# PSU-triple-voltage.net
KiCad netlist of a schematic drawn in EAGLE
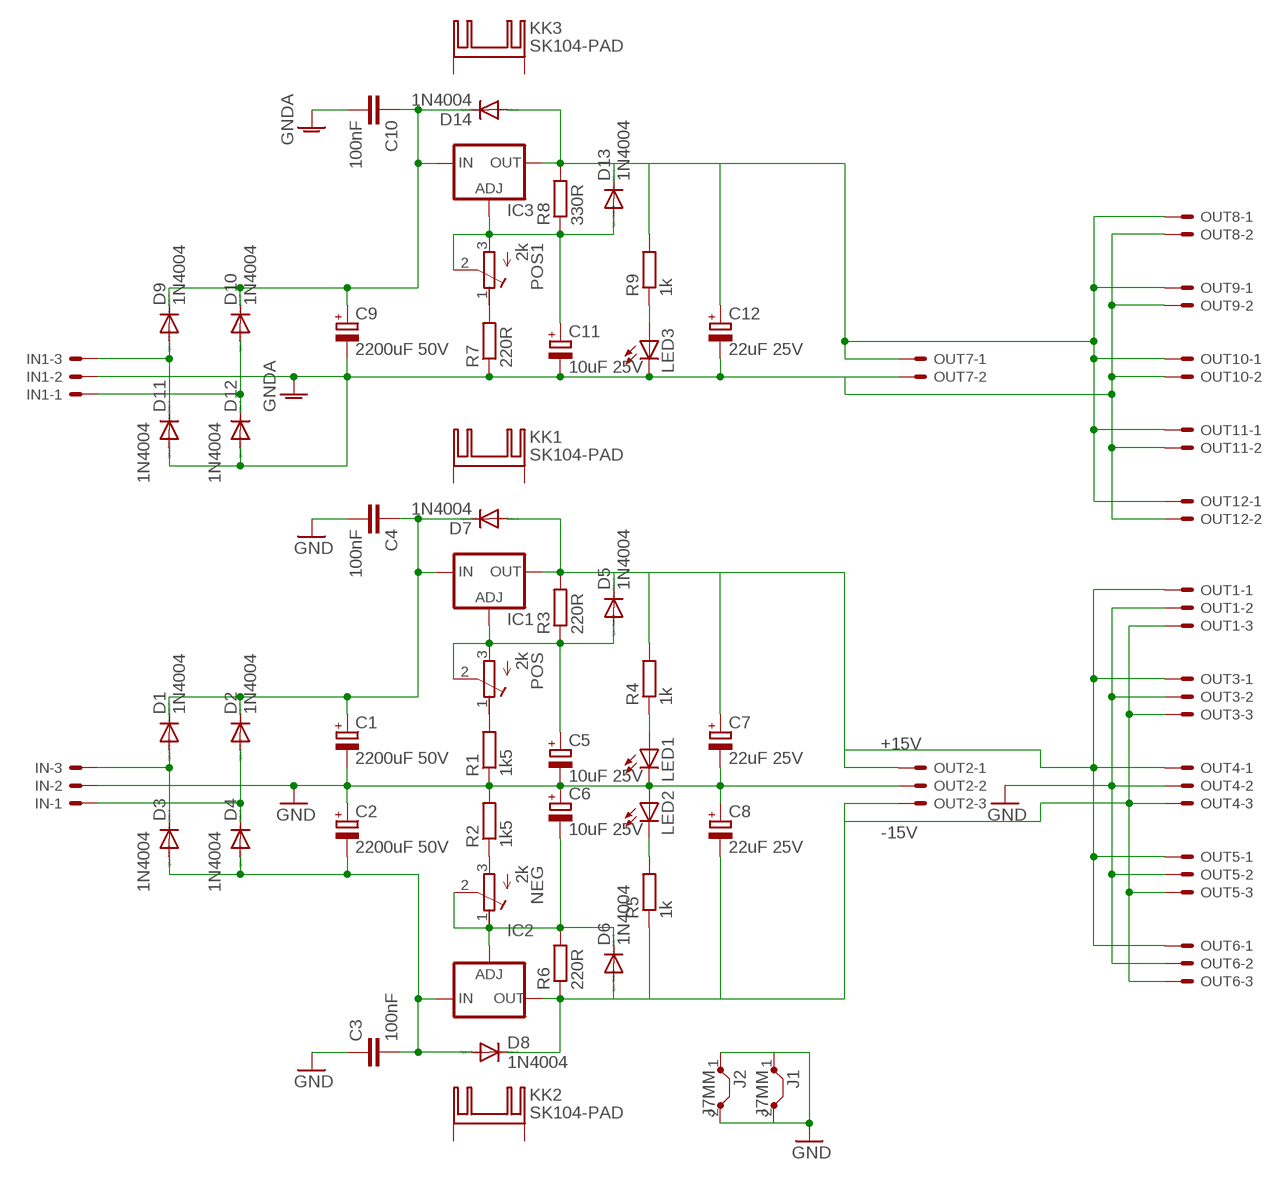
[diagram p0: schematic, sheet 1]

(export (version "E")
  (design (tool "Eeschema 10.0.6"))
  (components
    (comp (ref "C1")
      (value "2200uF 50V")
      (footprint "eagle-import:E7,5-16")
      (libsource (lib "eagle-import") (part "CPOL-EUE7.5-16"))
    )
    (comp (ref "C2")
      (value "2200uF 50V")
      (footprint "eagle-import:E7,5-16")
      (libsource (lib "eagle-import") (part "CPOL-EUE7.5-16"))
    )
    (comp (ref "C3")
      (value "100nF")
      (footprint "eagle-import:C050-025X075")
      (libsource (lib "eagle-import") (part "C-EU050-025X075"))
    )
    (comp (ref "C4")
      (value "100nF")
      (footprint "eagle-import:C050-025X075")
      (libsource (lib "eagle-import") (part "C-EU050-025X075"))
    )
    (comp (ref "C5")
      (value "10uF 25V")
      (footprint "eagle-import:E2,5-5")
      (libsource (lib "eagle-import") (part "CPOL-EUE2.5-5"))
    )
    (comp (ref "C6")
      (value "10uF 25V")
      (footprint "eagle-import:E2,5-5")
      (libsource (lib "eagle-import") (part "CPOL-EUE2.5-5"))
    )
    (comp (ref "C7")
      (value "22uF 25V")
      (footprint "eagle-import:E2,5-5")
      (libsource (lib "eagle-import") (part "CPOL-EUE2.5-5"))
    )
    (comp (ref "C8")
      (value "22uF 25V")
      (footprint "eagle-import:E2,5-5")
      (libsource (lib "eagle-import") (part "CPOL-EUE2.5-5"))
    )
    (comp (ref "C9")
      (value "2200uF 50V")
      (footprint "eagle-import:E7,5-16")
      (libsource (lib "eagle-import") (part "CPOL-EUE7.5-16"))
    )
    (comp (ref "C10")
      (value "100nF")
      (footprint "eagle-import:C050-025X075")
      (libsource (lib "eagle-import") (part "C-EU050-025X075"))
    )
    (comp (ref "C11")
      (value "10uF 25V")
      (footprint "eagle-import:E2,5-5")
      (libsource (lib "eagle-import") (part "CPOL-EUE2.5-5"))
    )
    (comp (ref "C12")
      (value "22uF 25V")
      (footprint "eagle-import:E2,5-5")
      (libsource (lib "eagle-import") (part "CPOL-EUE2.5-5"))
    )
    (comp (ref "D1")
      (value "1N4004")
      (footprint "eagle-import:DO41-10")
      (libsource (lib "eagle-import") (part "1N4004"))
    )
    (comp (ref "D2")
      (value "1N4004")
      (footprint "eagle-import:DO41-10")
      (libsource (lib "eagle-import") (part "1N4004"))
    )
    (comp (ref "D3")
      (value "1N4004")
      (footprint "eagle-import:DO41-10")
      (libsource (lib "eagle-import") (part "1N4004"))
    )
    (comp (ref "D4")
      (value "1N4004")
      (footprint "eagle-import:DO41-10")
      (libsource (lib "eagle-import") (part "1N4004"))
    )
    (comp (ref "D5")
      (value "1N4004")
      (footprint "eagle-import:DO41-10")
      (libsource (lib "eagle-import") (part "1N4004"))
    )
    (comp (ref "D6")
      (value "1N4004")
      (footprint "eagle-import:DO41-10")
      (libsource (lib "eagle-import") (part "1N4004"))
    )
    (comp (ref "D7")
      (value "1N4004")
      (footprint "eagle-import:DO41-10")
      (libsource (lib "eagle-import") (part "1N4004"))
    )
    (comp (ref "D8")
      (value "1N4004")
      (footprint "eagle-import:DO41-10")
      (libsource (lib "eagle-import") (part "1N4004"))
    )
    (comp (ref "D9")
      (value "1N4004")
      (footprint "eagle-import:DO41-10")
      (libsource (lib "eagle-import") (part "1N4004"))
    )
    (comp (ref "D10")
      (value "1N4004")
      (footprint "eagle-import:DO41-10")
      (libsource (lib "eagle-import") (part "1N4004"))
    )
    (comp (ref "D11")
      (value "1N4004")
      (footprint "eagle-import:DO41-10")
      (libsource (lib "eagle-import") (part "1N4004"))
    )
    (comp (ref "D12")
      (value "1N4004")
      (footprint "eagle-import:DO41-10")
      (libsource (lib "eagle-import") (part "1N4004"))
    )
    (comp (ref "D13")
      (value "1N4004")
      (footprint "eagle-import:DO41-10")
      (libsource (lib "eagle-import") (part "1N4004"))
    )
    (comp (ref "D14")
      (value "1N4004")
      (footprint "eagle-import:DO41-10")
      (libsource (lib "eagle-import") (part "1N4004"))
    )
    (comp (ref "IC1")
      (value "LM317TS")
      (footprint "eagle-import:317TS")
      (libsource (lib "eagle-import") (part "LM317TS"))
    )
    (comp (ref "IC2")
      (value "LM337TS")
      (footprint "eagle-import:337TS")
      (libsource (lib "eagle-import") (part "LM337TS"))
    )
    (comp (ref "IC3")
      (value "LM317TS")
      (footprint "eagle-import:317TS")
      (libsource (lib "eagle-import") (part "LM317TS"))
    )
    (comp (ref "IN")
      (value "KK-156-3")
      (footprint "eagle-import:KK-156-3")
      (libsource (lib "eagle-import") (part "KK-156-3"))
    )
    (comp (ref "IN1")
      (value "KK-156-3")
      (footprint "eagle-import:KK-156-3")
      (libsource (lib "eagle-import") (part "KK-156-3"))
    )
    (comp (ref "J1")
      (value "J7MM")
      (footprint "eagle-import:07")
      (libsource (lib "eagle-import") (part "J7MM"))
    )
    (comp (ref "J2")
      (value "J7MM")
      (footprint "eagle-import:07")
      (libsource (lib "eagle-import") (part "J7MM"))
    )
    (comp (ref "KK1")
      (value "SK104-PAD")
      (footprint "eagle-import:SK104-PAD")
      (libsource (lib "eagle-import") (part "SK104-PAD"))
    )
    (comp (ref "KK2")
      (value "SK104-PAD")
      (footprint "eagle-import:SK104-PAD")
      (libsource (lib "eagle-import") (part "SK104-PAD"))
    )
    (comp (ref "KK3")
      (value "SK104-PAD")
      (footprint "eagle-import:SK104-PAD")
      (libsource (lib "eagle-import") (part "SK104-PAD"))
    )
    (comp (ref "LED1")
      (value "LED3MM")
      (footprint "eagle-import:LED3MM")
      (libsource (lib "eagle-import") (part "LED3MM"))
    )
    (comp (ref "LED2")
      (value "LED3MM")
      (footprint "eagle-import:LED3MM")
      (libsource (lib "eagle-import") (part "LED3MM"))
    )
    (comp (ref "LED3")
      (value "LED3MM")
      (footprint "eagle-import:LED3MM")
      (libsource (lib "eagle-import") (part "LED3MM"))
    )
    (comp (ref "NEG")
      (value "2k")
      (footprint "eagle-import:RTRIMT93YA")
      (libsource (lib "eagle-import") (part "R-TRIMMT93YA"))
    )
    (comp (ref "OUT1")
      (value "KK-156-3")
      (footprint "eagle-import:KK-156-3")
      (libsource (lib "eagle-import") (part "KK-156-3"))
    )
    (comp (ref "OUT2")
      (value "KK-156-3")
      (footprint "eagle-import:KK-156-3")
      (libsource (lib "eagle-import") (part "KK-156-3"))
    )
    (comp (ref "OUT3")
      (value "KK-156-3")
      (footprint "eagle-import:KK-156-3")
      (libsource (lib "eagle-import") (part "KK-156-3"))
    )
    (comp (ref "OUT4")
      (value "KK-156-3")
      (footprint "eagle-import:KK-156-3")
      (libsource (lib "eagle-import") (part "KK-156-3"))
    )
    (comp (ref "OUT5")
      (value "KK-156-3")
      (footprint "eagle-import:KK-156-3")
      (libsource (lib "eagle-import") (part "KK-156-3"))
    )
    (comp (ref "OUT6")
      (value "KK-156-3")
      (footprint "eagle-import:KK-156-3")
      (libsource (lib "eagle-import") (part "KK-156-3"))
    )
    (comp (ref "OUT7")
      (value "KK-156-2")
      (footprint "eagle-import:KK-156-2")
      (libsource (lib "eagle-import") (part "KK-156-2"))
    )
    (comp (ref "OUT8")
      (value "KK-156-2")
      (footprint "eagle-import:KK-156-2")
      (libsource (lib "eagle-import") (part "KK-156-2"))
    )
    (comp (ref "OUT9")
      (value "KK-156-2")
      (footprint "eagle-import:KK-156-2")
      (libsource (lib "eagle-import") (part "KK-156-2"))
    )
    (comp (ref "OUT10")
      (value "KK-156-2")
      (footprint "eagle-import:KK-156-2")
      (libsource (lib "eagle-import") (part "KK-156-2"))
    )
    (comp (ref "OUT11")
      (value "KK-156-2")
      (footprint "eagle-import:KK-156-2")
      (libsource (lib "eagle-import") (part "KK-156-2"))
    )
    (comp (ref "OUT12")
      (value "KK-156-2")
      (footprint "eagle-import:KK-156-2")
      (libsource (lib "eagle-import") (part "KK-156-2"))
    )
    (comp (ref "POS")
      (value "2k")
      (footprint "eagle-import:RTRIMT93YA")
      (libsource (lib "eagle-import") (part "R-TRIMMT93YA"))
    )
    (comp (ref "POS1")
      (value "2k")
      (footprint "eagle-import:RTRIMT93YA")
      (libsource (lib "eagle-import") (part "R-TRIMMT93YA"))
    )
    (comp (ref "R1")
      (value "1k5")
      (footprint "eagle-import:0207_7")
      (libsource (lib "eagle-import") (part "R-EU_0207/7"))
    )
    (comp (ref "R2")
      (value "1k5")
      (footprint "eagle-import:0207_7")
      (libsource (lib "eagle-import") (part "R-EU_0207/7"))
    )
    (comp (ref "R3")
      (value "220R")
      (footprint "eagle-import:0207_7")
      (libsource (lib "eagle-import") (part "R-EU_0207/7"))
    )
    (comp (ref "R4")
      (value "1k")
      (footprint "eagle-import:0207_7")
      (libsource (lib "eagle-import") (part "R-EU_0207/7"))
    )
    (comp (ref "R5")
      (value "1k")
      (footprint "eagle-import:0207_7")
      (libsource (lib "eagle-import") (part "R-EU_0207/7"))
    )
    (comp (ref "R6")
      (value "220R")
      (footprint "eagle-import:0207_7")
      (libsource (lib "eagle-import") (part "R-EU_0207/7"))
    )
    (comp (ref "R7")
      (value "220R")
      (footprint "eagle-import:0207_7")
      (libsource (lib "eagle-import") (part "R-EU_0207/7"))
    )
    (comp (ref "R8")
      (value "330R")
      (footprint "eagle-import:0207_7")
      (libsource (lib "eagle-import") (part "R-EU_0207/7"))
    )
    (comp (ref "R9")
      (value "1k")
      (footprint "eagle-import:0207_7")
      (libsource (lib "eagle-import") (part "R-EU_0207/7"))
    )
  )
  (nets
    (net (code "1") (name "/+15V") (class "Default")
      (node (ref "C7") (pin "+") (pinfunction "+_+") (pintype "passive"))
      (node (ref "D5") (pin "C") (pinfunction "C_C") (pintype "passive"))
      (node (ref "D7") (pin "A") (pinfunction "A_A") (pintype "passive"))
      (node (ref "IC1") (pin "2") (pinfunction "OUT_2") (pintype "passive"))
      (node (ref "OUT1") (pin "1") (pinfunction "S_1") (pintype "passive"))
      (node (ref "OUT2") (pin "1") (pinfunction "S_1") (pintype "passive"))
      (node (ref "OUT3") (pin "1") (pinfunction "S_1") (pintype "passive"))
      (node (ref "OUT4") (pin "1") (pinfunction "S_1") (pintype "passive"))
      (node (ref "OUT5") (pin "1") (pinfunction "S_1") (pintype "passive"))
      (node (ref "OUT6") (pin "1") (pinfunction "S_1") (pintype "passive"))
      (node (ref "R3") (pin "2") (pinfunction "2_2") (pintype "passive"))
      (node (ref "R4") (pin "2") (pinfunction "2_2") (pintype "passive"))
    )
    (net (code "2") (name "/-15V") (class "Default")
      (node (ref "C8") (pin "-") (pinfunction "-_-") (pintype "passive"))
      (node (ref "D6") (pin "A") (pinfunction "A_A") (pintype "passive"))
      (node (ref "D8") (pin "C") (pinfunction "C_C") (pintype "passive"))
      (node (ref "IC2") (pin "3") (pinfunction "OUT_3") (pintype "passive"))
      (node (ref "OUT1") (pin "3") (pinfunction "S_3") (pintype "passive"))
      (node (ref "OUT2") (pin "3") (pinfunction "S_3") (pintype "passive"))
      (node (ref "OUT3") (pin "3") (pinfunction "S_3") (pintype "passive"))
      (node (ref "OUT4") (pin "3") (pinfunction "S_3") (pintype "passive"))
      (node (ref "OUT5") (pin "3") (pinfunction "S_3") (pintype "passive"))
      (node (ref "OUT6") (pin "3") (pinfunction "S_3") (pintype "passive"))
      (node (ref "R5") (pin "1") (pinfunction "1_1") (pintype "passive"))
      (node (ref "R6") (pin "1") (pinfunction "1_1") (pintype "passive"))
    )
    (net (code "3") (name "GND") (class "Default")
      (node (ref "C1") (pin "-") (pinfunction "-_-") (pintype "passive"))
      (node (ref "C2") (pin "+") (pinfunction "+_+") (pintype "passive"))
      (node (ref "C3") (pin "1") (pinfunction "1_1") (pintype "passive"))
      (node (ref "C4") (pin "2") (pinfunction "2_2") (pintype "passive"))
      (node (ref "C5") (pin "-") (pinfunction "-_-") (pintype "passive"))
      (node (ref "C6") (pin "+") (pinfunction "+_+") (pintype "passive"))
      (node (ref "C7") (pin "-") (pinfunction "-_-") (pintype "passive"))
      (node (ref "C8") (pin "+") (pinfunction "+_+") (pintype "passive"))
      (node (ref "IN") (pin "2") (pinfunction "S_2") (pintype "passive"))
      (node (ref "J1") (pin "1") (pinfunction "1_1") (pintype "passive"))
      (node (ref "J1") (pin "2") (pinfunction "2_2") (pintype "passive"))
      (node (ref "J2") (pin "1") (pinfunction "1_1") (pintype "passive"))
      (node (ref "J2") (pin "2") (pinfunction "2_2") (pintype "passive"))
      (node (ref "LED1") (pin "K") (pinfunction "C_K") (pintype "passive"))
      (node (ref "LED2") (pin "A") (pinfunction "A_A") (pintype "passive"))
      (node (ref "OUT1") (pin "2") (pinfunction "S_2") (pintype "passive"))
      (node (ref "OUT2") (pin "2") (pinfunction "S_2") (pintype "passive"))
      (node (ref "OUT3") (pin "2") (pinfunction "S_2") (pintype "passive"))
      (node (ref "OUT4") (pin "2") (pinfunction "S_2") (pintype "passive"))
      (node (ref "OUT5") (pin "2") (pinfunction "S_2") (pintype "passive"))
      (node (ref "OUT6") (pin "2") (pinfunction "S_2") (pintype "passive"))
      (node (ref "R1") (pin "1") (pinfunction "1_1") (pintype "passive"))
      (node (ref "R2") (pin "2") (pinfunction "2_2") (pintype "passive"))
    )
    (net (code "4") (name "GNDA") (class "Default")
      (node (ref "C10") (pin "2") (pinfunction "2_2") (pintype "passive"))
      (node (ref "C11") (pin "-") (pinfunction "-_-") (pintype "passive"))
      (node (ref "C12") (pin "-") (pinfunction "-_-") (pintype "passive"))
      (node (ref "C9") (pin "-") (pinfunction "-_-") (pintype "passive"))
      (node (ref "D11") (pin "A") (pinfunction "A_A") (pintype "passive"))
      (node (ref "D12") (pin "A") (pinfunction "A_A") (pintype "passive"))
      (node (ref "IN1") (pin "2") (pinfunction "S_2") (pintype "passive"))
      (node (ref "LED3") (pin "K") (pinfunction "C_K") (pintype "passive"))
      (node (ref "OUT10") (pin "2") (pinfunction "S_2") (pintype "passive"))
      (node (ref "OUT11") (pin "2") (pinfunction "S_2") (pintype "passive"))
      (node (ref "OUT12") (pin "2") (pinfunction "S_2") (pintype "passive"))
      (node (ref "OUT7") (pin "2") (pinfunction "S_2") (pintype "passive"))
      (node (ref "OUT8") (pin "2") (pinfunction "S_2") (pintype "passive"))
      (node (ref "OUT9") (pin "2") (pinfunction "S_2") (pintype "passive"))
      (node (ref "R7") (pin "1") (pinfunction "1_1") (pintype "passive"))
    )
    (net (code "5") (name "Net-(IC1-ADJ)") (class "Default")
      (node (ref "C5") (pin "+") (pinfunction "+_+") (pintype "passive"))
      (node (ref "D5") (pin "A") (pinfunction "A_A") (pintype "passive"))
      (node (ref "IC1") (pin "1") (pinfunction "ADJ_1") (pintype "input"))
      (node (ref "POS") (pin "2") (pinfunction "S_2") (pintype "passive"))
      (node (ref "POS") (pin "3") (pinfunction "A_3") (pintype "passive"))
      (node (ref "R3") (pin "1") (pinfunction "1_1") (pintype "passive"))
    )
    (net (code "6") (name "Net-(IC1-IN)") (class "Default")
      (node (ref "C1") (pin "+") (pinfunction "+_+") (pintype "passive"))
      (node (ref "C4") (pin "1") (pinfunction "1_1") (pintype "passive"))
      (node (ref "D1") (pin "C") (pinfunction "C_C") (pintype "passive"))
      (node (ref "D2") (pin "C") (pinfunction "C_C") (pintype "passive"))
      (node (ref "D7") (pin "C") (pinfunction "C_C") (pintype "passive"))
      (node (ref "IC1") (pin "3") (pinfunction "IN_3") (pintype "input"))
    )
    (net (code "7") (name "Net-(IC2-ADJ)") (class "Default")
      (node (ref "C6") (pin "-") (pinfunction "-_-") (pintype "passive"))
      (node (ref "D6") (pin "C") (pinfunction "C_C") (pintype "passive"))
      (node (ref "IC2") (pin "1") (pinfunction "ADJ_1") (pintype "input"))
      (node (ref "NEG") (pin "1") (pinfunction "E_1") (pintype "passive"))
      (node (ref "NEG") (pin "2") (pinfunction "S_2") (pintype "passive"))
      (node (ref "R6") (pin "2") (pinfunction "2_2") (pintype "passive"))
    )
    (net (code "8") (name "Net-(IC2-IN)") (class "Default")
      (node (ref "C2") (pin "-") (pinfunction "-_-") (pintype "passive"))
      (node (ref "C3") (pin "2") (pinfunction "2_2") (pintype "passive"))
      (node (ref "D3") (pin "A") (pinfunction "A_A") (pintype "passive"))
      (node (ref "D4") (pin "A") (pinfunction "A_A") (pintype "passive"))
      (node (ref "D8") (pin "A") (pinfunction "A_A") (pintype "passive"))
      (node (ref "IC2") (pin "2") (pinfunction "IN_2") (pintype "input"))
    )
    (net (code "9") (name "Net-(IC3-ADJ)") (class "Default")
      (node (ref "C11") (pin "+") (pinfunction "+_+") (pintype "passive"))
      (node (ref "D13") (pin "A") (pinfunction "A_A") (pintype "passive"))
      (node (ref "IC3") (pin "1") (pinfunction "ADJ_1") (pintype "input"))
      (node (ref "POS1") (pin "2") (pinfunction "S_2") (pintype "passive"))
      (node (ref "POS1") (pin "3") (pinfunction "A_3") (pintype "passive"))
      (node (ref "R8") (pin "1") (pinfunction "1_1") (pintype "passive"))
    )
    (net (code "10") (name "Net-(IC3-IN)") (class "Default")
      (node (ref "C10") (pin "1") (pinfunction "1_1") (pintype "passive"))
      (node (ref "C9") (pin "+") (pinfunction "+_+") (pintype "passive"))
      (node (ref "D10") (pin "C") (pinfunction "C_C") (pintype "passive"))
      (node (ref "D14") (pin "C") (pinfunction "C_C") (pintype "passive"))
      (node (ref "D9") (pin "C") (pinfunction "C_C") (pintype "passive"))
      (node (ref "IC3") (pin "3") (pinfunction "IN_3") (pintype "input"))
    )
    (net (code "11") (name "Net-(IC3-OUT)") (class "Default")
      (node (ref "C12") (pin "+") (pinfunction "+_+") (pintype "passive"))
      (node (ref "D13") (pin "C") (pinfunction "C_C") (pintype "passive"))
      (node (ref "D14") (pin "A") (pinfunction "A_A") (pintype "passive"))
      (node (ref "IC3") (pin "2") (pinfunction "OUT_2") (pintype "passive"))
      (node (ref "OUT10") (pin "1") (pinfunction "S_1") (pintype "passive"))
      (node (ref "OUT11") (pin "1") (pinfunction "S_1") (pintype "passive"))
      (node (ref "OUT12") (pin "1") (pinfunction "S_1") (pintype "passive"))
      (node (ref "OUT7") (pin "1") (pinfunction "S_1") (pintype "passive"))
      (node (ref "OUT8") (pin "1") (pinfunction "S_1") (pintype "passive"))
      (node (ref "OUT9") (pin "1") (pinfunction "S_1") (pintype "passive"))
      (node (ref "R8") (pin "2") (pinfunction "2_2") (pintype "passive"))
      (node (ref "R9") (pin "2") (pinfunction "2_2") (pintype "passive"))
    )
    (net (code "12") (name "Net-(IN1A-S)") (class "Default")
      (node (ref "D10") (pin "A") (pinfunction "A_A") (pintype "passive"))
      (node (ref "D12") (pin "C") (pinfunction "C_C") (pintype "passive"))
      (node (ref "IN1") (pin "1") (pinfunction "S_1") (pintype "passive"))
    )
    (net (code "13") (name "Net-(IN1C-S)") (class "Default")
      (node (ref "D11") (pin "C") (pinfunction "C_C") (pintype "passive"))
      (node (ref "D9") (pin "A") (pinfunction "A_A") (pintype "passive"))
      (node (ref "IN1") (pin "3") (pinfunction "S_3") (pintype "passive"))
    )
    (net (code "14") (name "Net-(INA-S)") (class "Default")
      (node (ref "D2") (pin "A") (pinfunction "A_A") (pintype "passive"))
      (node (ref "D4") (pin "C") (pinfunction "C_C") (pintype "passive"))
      (node (ref "IN") (pin "1") (pinfunction "S_1") (pintype "passive"))
    )
    (net (code "15") (name "Net-(INC-S)") (class "Default")
      (node (ref "D1") (pin "A") (pinfunction "A_A") (pintype "passive"))
      (node (ref "D3") (pin "C") (pinfunction "C_C") (pintype "passive"))
      (node (ref "IN") (pin "3") (pinfunction "S_3") (pintype "passive"))
    )
    (net (code "16") (name "Net-(LED1-PadA)") (class "Default")
      (node (ref "LED1") (pin "A") (pinfunction "A_A") (pintype "passive"))
      (node (ref "R4") (pin "1") (pinfunction "1_1") (pintype "passive"))
    )
    (net (code "17") (name "Net-(LED2-C)") (class "Default")
      (node (ref "LED2") (pin "K") (pinfunction "C_K") (pintype "passive"))
      (node (ref "R5") (pin "2") (pinfunction "2_2") (pintype "passive"))
    )
    (net (code "18") (name "Net-(LED3-PadA)") (class "Default")
      (node (ref "LED3") (pin "A") (pinfunction "A_A") (pintype "passive"))
      (node (ref "R9") (pin "1") (pinfunction "1_1") (pintype "passive"))
    )
    (net (code "19") (name "Net-(NEG-A)") (class "Default")
      (node (ref "NEG") (pin "3") (pinfunction "A_3") (pintype "passive"))
      (node (ref "R2") (pin "1") (pinfunction "1_1") (pintype "passive"))
    )
    (net (code "20") (name "Net-(POS-E)") (class "Default")
      (node (ref "POS") (pin "1") (pinfunction "E_1") (pintype "passive"))
      (node (ref "R1") (pin "2") (pinfunction "2_2") (pintype "passive"))
    )
    (net (code "21") (name "Net-(POS1-E)") (class "Default")
      (node (ref "POS1") (pin "1") (pinfunction "E_1") (pintype "passive"))
      (node (ref "R7") (pin "2") (pinfunction "2_2") (pintype "passive"))
    )
    (net (code "22") (name "unconnected-(KK1-K-PadK1)") (class "Default")
      (node (ref "KK1") (pin "K1") (pinfunction "K_K1") (pintype "passive"))
    )
    (net (code "23") (name "unconnected-(KK1-K-PadK2)") (class "Default")
      (node (ref "KK1") (pin "K2") (pinfunction "K_K2") (pintype "passive"))
    )
    (net (code "24") (name "unconnected-(KK2-K-PadK1)") (class "Default")
      (node (ref "KK2") (pin "K1") (pinfunction "K_K1") (pintype "passive"))
    )
    (net (code "25") (name "unconnected-(KK2-K-PadK2)") (class "Default")
      (node (ref "KK2") (pin "K2") (pinfunction "K_K2") (pintype "passive"))
    )
    (net (code "26") (name "unconnected-(KK3-K-PadK1)") (class "Default")
      (node (ref "KK3") (pin "K1") (pinfunction "K_K1") (pintype "passive"))
    )
    (net (code "27") (name "unconnected-(KK3-K-PadK2)") (class "Default")
      (node (ref "KK3") (pin "K2") (pinfunction "K_K2") (pintype "passive"))
    )
  )
)
